# Universal-Power-Board.net
KiCad netlist of a schematic drawn in Altium Designer
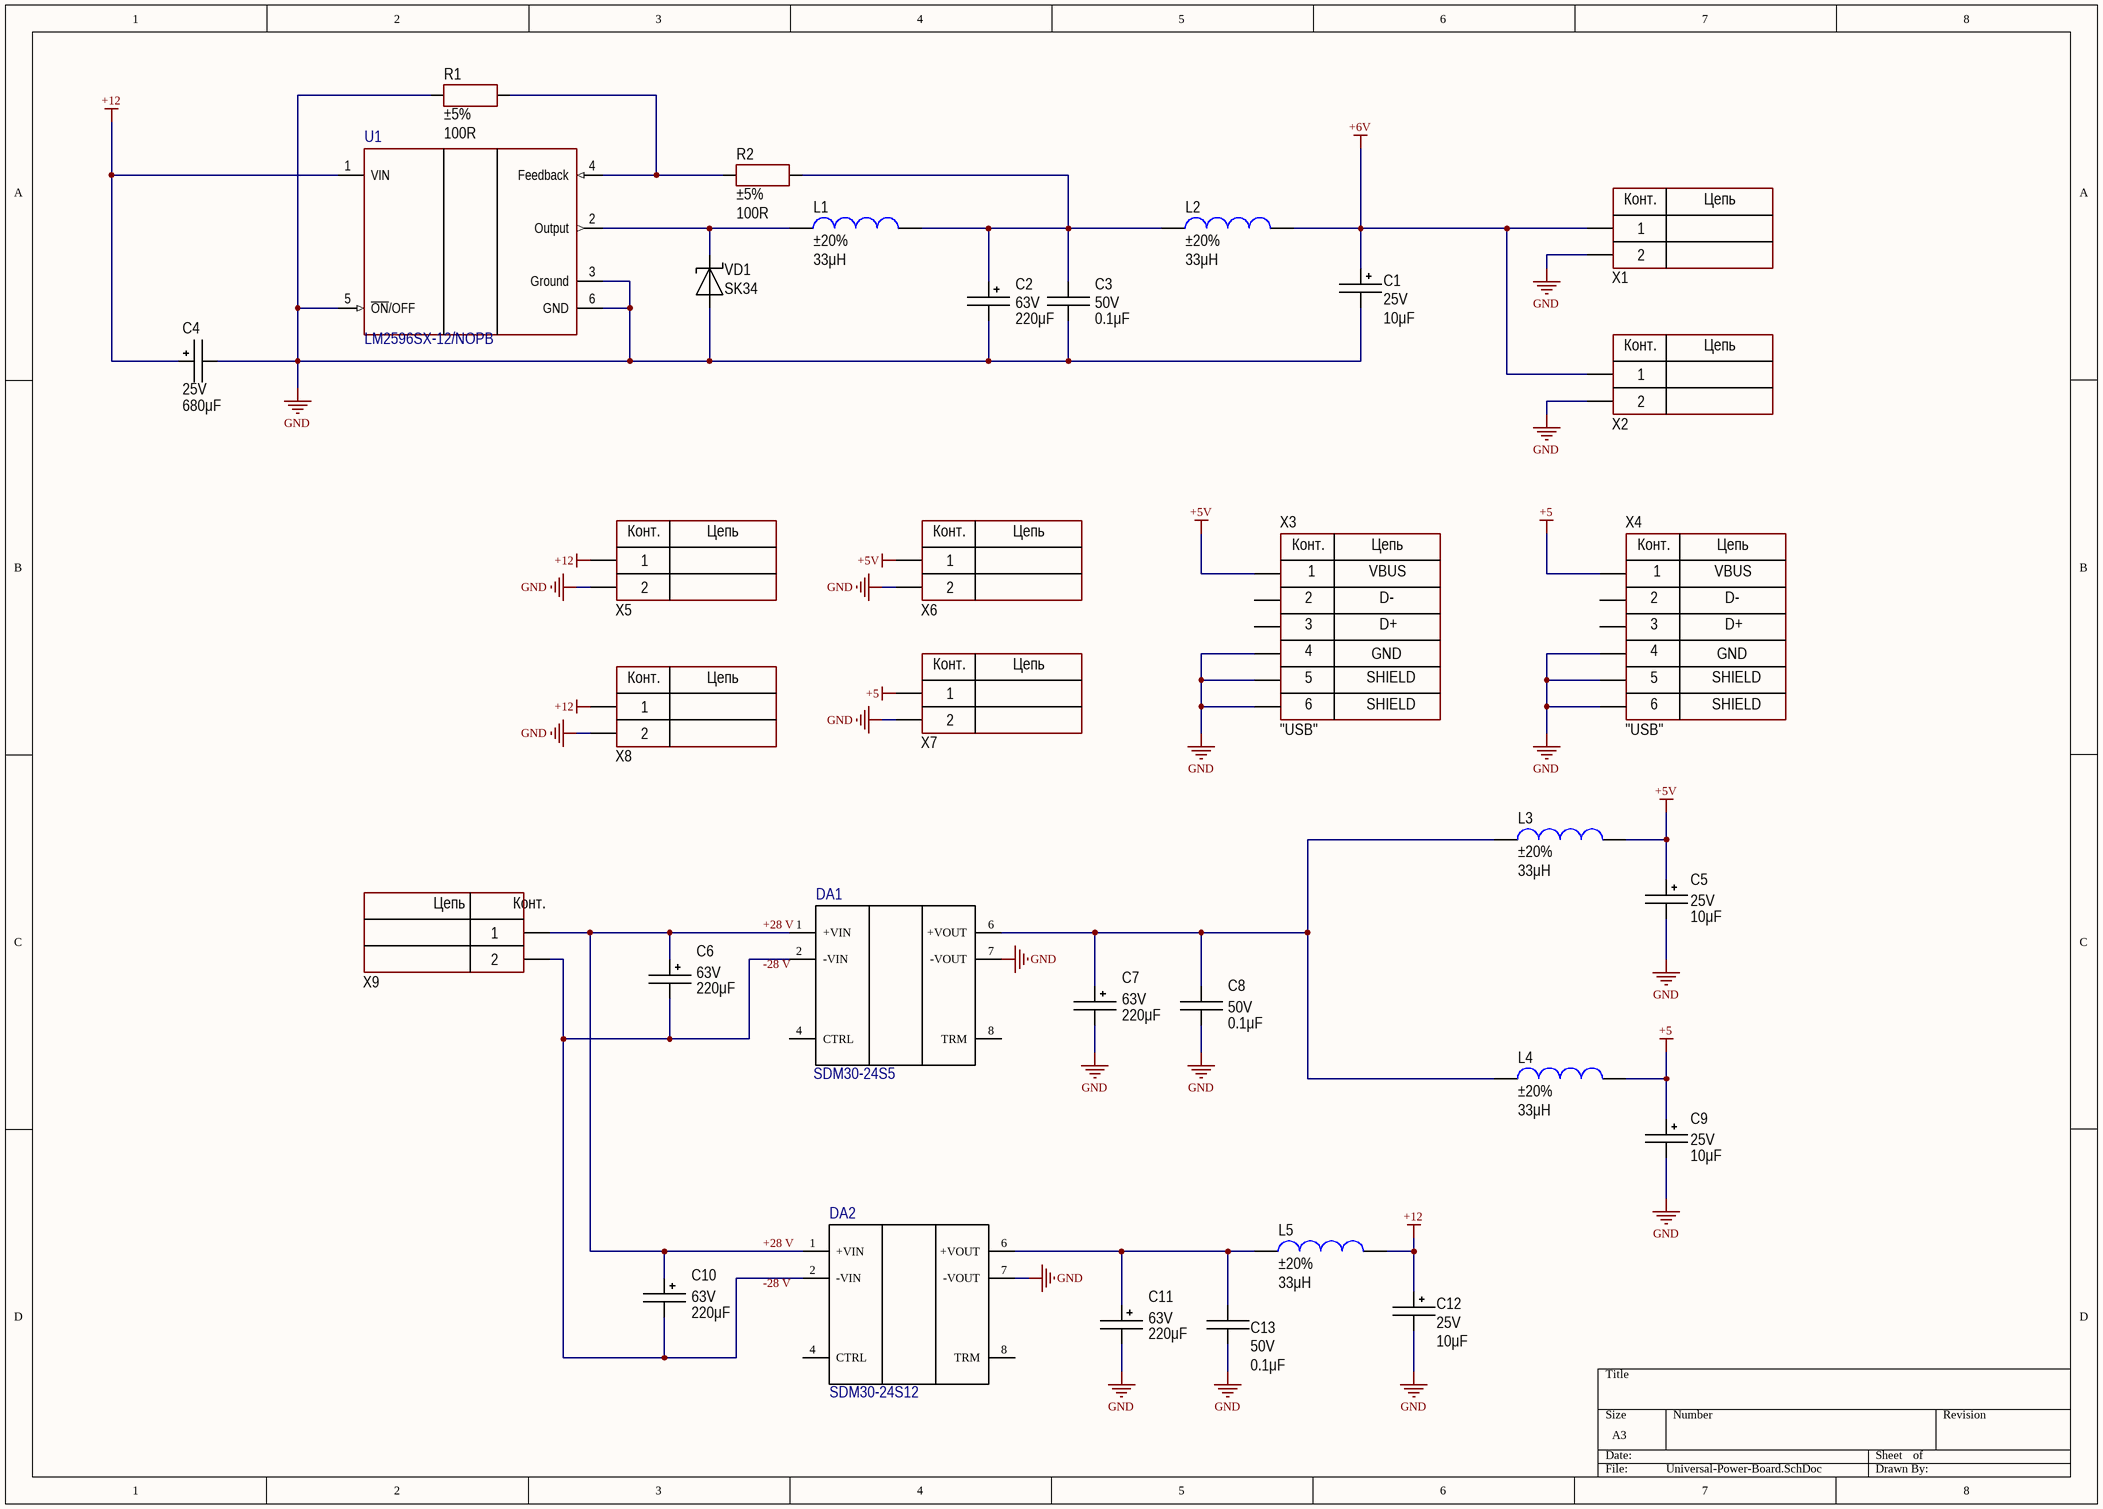
[diagram p0: Universal-Power-Board.SchDoc]

(export (version "E")
  (design (tool "Eeschema 10.0.6"))
  (components
    (comp (ref "C1")
      (value "10μF")
      (footprint "standard-case:CAP: D6.3C2.5H11")
      (fields
        (field (name "MANUFACTURER") "Wurth")
        (field (name "PARTNUMBER") "860080475013")
        (field (name "VALUEMANUFACTURERPARTNUMBER") "Aluminium capacitor, 10μF, 25V, ±20%, 54mOhm, 14x10x5 mm, -55...+105°C")
        (field (name "VOLTAGE") "25V")
      )
      (libsource (lib "capacitor") (part "Aluminium"))
    )
    (comp (ref "C2")
      (value "220μF")
      (footprint "standard-case:CAP: D10C5H16")
      (fields
        (field (name "MANUFACTURER") "Wurth")
        (field (name "PARTNUMBER") "860080475013")
        (field (name "VALUEMANUFACTURERPARTNUMBER") "Aluminium capacitor, 220μF, 63V, ±20%, 54mOhm, 14x10x5 mm, -55...+105°C")
        (field (name "VOLTAGE") "63V")
      )
      (libsource (lib "capacitor") (part "Aluminium"))
    )
    (comp (ref "C3")
      (value "0.1μF")
      (footprint "standard-case:CAP: 1206")
      (fields
        (field (name "MANUFACTURER") "Yageo")
        (field (name "PARTNUMBER") "CC1206KRX7R9BB104")
        (field (name "VALUEMANUFACTURERPARTNUMBER") "Ceramic capacitor, 0.1μF, X7R, ±10%, 50V, 1206, -55...+125°C")
        (field (name "VOLTAGE") "50V")
      )
      (libsource (lib "capacitor") (part "Ceramic_1206"))
    )
    (comp (ref "C4")
      (value "680μF")
      (footprint "standard-case:CAP: D10C5H16")
      (fields
        (field (name "MANUFACTURER") "Wurth")
        (field (name "PARTNUMBER") "860080475013")
        (field (name "VALUEMANUFACTURERPARTNUMBER") "Aluminium capacitor, 680μF, 25V, ±20%, 54mOhm, 14x10x5 mm, -55...+105°C")
        (field (name "VOLTAGE") "25V")
      )
      (libsource (lib "capacitor") (part "Aluminium"))
    )
    (comp (ref "C5")
      (value "10μF")
      (footprint "standard-case:CAP: D6.3C2.5H11")
      (fields
        (field (name "MANUFACTURER") "Wurth")
        (field (name "PARTNUMBER") "860080475013")
        (field (name "VALUEMANUFACTURERPARTNUMBER") "Aluminium capacitor, 10μF, 25V, ±20%, 54mOhm, 14x10x5 mm, -55...+105°C")
        (field (name "VOLTAGE") "25V")
      )
      (libsource (lib "capacitor") (part "Aluminium"))
    )
    (comp (ref "C6")
      (value "220μF")
      (footprint "standard-case:CAP: D10C5H16")
      (fields
        (field (name "MANUFACTURER") "Wurth")
        (field (name "PARTNUMBER") "860080475013")
        (field (name "VALUEMANUFACTURERPARTNUMBER") "Aluminium capacitor, 220μF, 63V, ±20%, 54mOhm, 14x10x5 mm, -55...+105°C")
        (field (name "VOLTAGE") "63V")
      )
      (libsource (lib "capacitor") (part "Aluminium"))
    )
    (comp (ref "C7")
      (value "220μF")
      (footprint "standard-case:CAP: D10C5H16")
      (fields
        (field (name "MANUFACTURER") "Wurth")
        (field (name "PARTNUMBER") "860080475013")
        (field (name "VALUEMANUFACTURERPARTNUMBER") "Aluminium capacitor, 220μF, 63V, ±20%, 54mOhm, 14x10x5 mm, -55...+105°C")
        (field (name "VOLTAGE") "63V")
      )
      (libsource (lib "capacitor") (part "Aluminium"))
    )
    (comp (ref "C8")
      (value "0.1μF")
      (footprint "standard-case:CAP: 1206")
      (fields
        (field (name "MANUFACTURER") "Yageo")
        (field (name "PARTNUMBER") "CC1206KRX7R9BB104")
        (field (name "VALUEMANUFACTURERPARTNUMBER") "Ceramic capacitor, 0.1μF, X7R, ±10%, 50V, 1206, -55...+125°C")
        (field (name "VOLTAGE") "50V")
      )
      (libsource (lib "capacitor") (part "Ceramic_1206"))
    )
    (comp (ref "C9")
      (value "10μF")
      (footprint "standard-case:CAP: D6.3C2.5H11")
      (fields
        (field (name "MANUFACTURER") "Wurth")
        (field (name "PARTNUMBER") "860080475013")
        (field (name "VALUEMANUFACTURERPARTNUMBER") "Aluminium capacitor, 10μF, 25V, ±20%, 54mOhm, 14x10x5 mm, -55...+105°C")
        (field (name "VOLTAGE") "25V")
      )
      (libsource (lib "capacitor") (part "Aluminium"))
    )
    (comp (ref "C10")
      (value "220μF")
      (footprint "standard-case:CAP: D10C5H16")
      (fields
        (field (name "MANUFACTURER") "Wurth")
        (field (name "PARTNUMBER") "860080475013")
        (field (name "VALUEMANUFACTURERPARTNUMBER") "Aluminium capacitor, 220μF, 63V, ±20%, 54mOhm, 14x10x5 mm, -55...+105°C")
        (field (name "VOLTAGE") "63V")
      )
      (libsource (lib "capacitor") (part "Aluminium"))
    )
    (comp (ref "C11")
      (value "220μF")
      (footprint "standard-case:CAP: D10C5H16")
      (fields
        (field (name "MANUFACTURER") "Wurth")
        (field (name "PARTNUMBER") "860080475013")
        (field (name "VALUEMANUFACTURERPARTNUMBER") "Aluminium capacitor, 220μF, 63V, ±20%, 54mOhm, 14x10x5 mm, -55...+105°C")
        (field (name "VOLTAGE") "63V")
      )
      (libsource (lib "capacitor") (part "Aluminium"))
    )
    (comp (ref "C12")
      (value "10μF")
      (footprint "standard-case:CAP: D6.3C2.5H11")
      (fields
        (field (name "MANUFACTURER") "Wurth")
        (field (name "PARTNUMBER") "860080475013")
        (field (name "VALUEMANUFACTURERPARTNUMBER") "Aluminium capacitor, 10μF, 25V, ±20%, 54mOhm, 14x10x5 mm, -55...+105°C")
        (field (name "VOLTAGE") "25V")
      )
      (libsource (lib "capacitor") (part "Aluminium"))
    )
    (comp (ref "C13")
      (value "0.1μF")
      (footprint "standard-case:CAP: 1206")
      (fields
        (field (name "MANUFACTURER") "Yageo")
        (field (name "PARTNUMBER") "CC1206KRX7R9BB104")
        (field (name "VALUEMANUFACTURERPARTNUMBER") "Ceramic capacitor, 0.1μF, X7R, ±10%, 50V, 1206, -55...+125°C")
        (field (name "VOLTAGE") "50V")
      )
      (libsource (lib "capacitor") (part "Ceramic_1206"))
    )
    (comp (ref "DA1")
      (value "SDM30-24S5")
      (footprint "SDM3024S5")
      (description "Power Supply")
      (libsource (lib "SDM30-24S5") (part "SDM30-24S5"))
    )
    (comp (ref "DA2")
      (value "SDM30-24S12")
      (footprint "SDM3024S12")
      (description "Power Supply")
      (libsource (lib "SDM30-24S12") (part "SDM30-24S12"))
    )
    (comp (ref "L1")
      (value "33μH")
      (footprint "SRR1208-101YL")
      (fields
        (field (name "MANUFACTURER") "Bourns")
        (field (name "PARTNUMBER") "SDR0403-4R7ML")
        (field (name "VALUEMANUFACTURERPARTNUMBER") "Fixed inductor, 33μH, ±20%, SDR0403, 1.7A, -40...+125°C")
        (field (name "TOLERANCE") "±20%")
      )
      (libsource (lib "SRR1208-101YL") (part "Inductor_SDR0403"))
    )
    (comp (ref "L2")
      (value "33μH")
      (footprint "SRR1208-101YL")
      (fields
        (field (name "MANUFACTURER") "Bourns")
        (field (name "PARTNUMBER") "SDR0403-4R7ML")
        (field (name "VALUEMANUFACTURERPARTNUMBER") "Fixed inductor, 33μH, ±20%, SDR0403, 1.7A, -40...+125°C")
        (field (name "TOLERANCE") "±20%")
      )
      (libsource (lib "SRR1208-101YL") (part "Inductor_SDR0403"))
    )
    (comp (ref "L3")
      (value "33μH")
      (footprint "SRR1208-101YL")
      (fields
        (field (name "MANUFACTURER") "Bourns")
        (field (name "PARTNUMBER") "SDR0403-4R7ML")
        (field (name "VALUEMANUFACTURERPARTNUMBER") "Fixed inductor, 33μH, ±20%, SDR0403, 1.7A, -40...+125°C")
        (field (name "TOLERANCE") "±20%")
      )
      (libsource (lib "SRR1208-101YL") (part "Inductor_SDR0403"))
    )
    (comp (ref "L4")
      (value "33μH")
      (footprint "SRR1208-101YL")
      (fields
        (field (name "MANUFACTURER") "Bourns")
        (field (name "PARTNUMBER") "SDR0403-4R7ML")
        (field (name "VALUEMANUFACTURERPARTNUMBER") "Fixed inductor, 33μH, ±20%, SDR0403, 1.7A, -40...+125°C")
        (field (name "TOLERANCE") "±20%")
      )
      (libsource (lib "SRR1208-101YL") (part "Inductor_SDR0403"))
    )
    (comp (ref "L5")
      (value "33μH")
      (footprint "SRR1208-101YL")
      (fields
        (field (name "MANUFACTURER") "Bourns")
        (field (name "PARTNUMBER") "SDR0403-4R7ML")
        (field (name "VALUEMANUFACTURERPARTNUMBER") "Fixed inductor, 33μH, ±20%, SDR0403, 1.7A, -40...+125°C")
        (field (name "TOLERANCE") "±20%")
      )
      (libsource (lib "SRR1208-101YL") (part "Inductor_SDR0403"))
    )
    (comp (ref "R1")
      (value "100R")
      (footprint "standard-case:RES: 1206")
      (fields
        (field (name "MANUFACTURER") "Yageo")
        (field (name "PARTNUMBER") "RC1206JR-07100RL")
        (field (name "VALUEMANUFACTURERPARTNUMBER") "Resistor film, 100R, ±5%, 1206, 0.25W, -55...+125°C")
        (field (name "TOLERANCE") "±5%")
      )
      (libsource (lib "resistor") (part "Resistor_1206"))
    )
    (comp (ref "R2")
      (value "100R")
      (footprint "standard-case:RES: 1206")
      (fields
        (field (name "MANUFACTURER") "Yageo")
        (field (name "PARTNUMBER") "RC1206JR-07100RL")
        (field (name "VALUEMANUFACTURERPARTNUMBER") "Resistor film, 100R, ±5%, 1206, 0.25W, -55...+125°C")
        (field (name "TOLERANCE") "±5%")
      )
      (libsource (lib "resistor") (part "Resistor_1206"))
    )
    (comp (ref "U1")
      (value "LM2596SX-12/NOPB")
      (footprint "FP-KTT0005B-MFG")
      (description "IC REG BUCK 12V 3A TO263-5")
      (fields
        (field (name "MANUFACTURER") "Texas Instruments")
        (field (name "OCTOPART") "https://octopart.com/lm2596sx-12%2Fnopb-texas+instruments-24812942")
      )
      (libsource (lib "LM2596SX-12NOPB") (part "CMP-04918-000013-1"))
    )
    (comp (ref "VD1")
      (value "~")
      (footprint "standard-case:DIODE: SMC")
      (fields
        (field (name "MANUFACTURER") "Diodes Incorporated")
        (field (name "VALUEMANUFACTURERPARTNUMBER") "Schottky diode, 80V, 500mA, 1V, 15pF, SOD-123, -55...+150°C")
        (field (name "VOLTAGE") "80V")
        (field (name "PARTNUMBER") "SK34")
      )
      (libsource (lib "diode") (part "Schottky_single"))
    )
    (comp (ref "X1")
      (value "~")
      (footprint "2EDGR-5.08-02P")
      (fields
        (field (name "MANUFACTURER") "Connfly")
        (field (name "VALUEMANUFACTURERPARTNUMBER") "Connector, 6pin, 2.54mm, 500VAC, 3A")
        (field (name "PARTNUMBER") "PBS-6")
      )
      (libsource (lib "K3NG_SCH_Libs") (part "2EDGR-5.08-02P"))
    )
    (comp (ref "X2")
      (value "~")
      (footprint "2EDGR-5.08-02P")
      (fields
        (field (name "MANUFACTURER") "Connfly")
        (field (name "VALUEMANUFACTURERPARTNUMBER") "Connector, 6pin, 2.54mm, 500VAC, 3A")
        (field (name "PARTNUMBER") "PBS-6")
      )
      (libsource (lib "K3NG_SCH_Libs") (part "2EDGR-5.08-02P"))
    )
    (comp (ref "X3")
      (value "~")
      (footprint "FP-292303-4-MFG")
      (fields
        (field (name "MANUFACTURER") "Hirose Electric")
        (field (name "VALUEMANUFACTURERPARTNUMBER") "USB micro B")
        (field (name "PARTNUMBER") "ZX62-B-5PA")
        (field (name "COMMENTTEXT") "\"USB\"")
      )
      (libsource (lib "292303-4") (part "Connector_USB_micro_B"))
    )
    (comp (ref "X4")
      (value "~")
      (footprint "FP-292303-4-MFG")
      (fields
        (field (name "MANUFACTURER") "Hirose Electric")
        (field (name "VALUEMANUFACTURERPARTNUMBER") "USB micro B")
        (field (name "PARTNUMBER") "ZX62-B-5PA")
        (field (name "COMMENTTEXT") "\"USB\"")
      )
      (libsource (lib "292303-4") (part "Connector_USB_micro_B"))
    )
    (comp (ref "X5")
      (value "~")
      (footprint "2EDGR-5.08-02P")
      (fields
        (field (name "MANUFACTURER") "Connfly")
        (field (name "VALUEMANUFACTURERPARTNUMBER") "Connector, 6pin, 2.54mm, 500VAC, 3A")
        (field (name "PARTNUMBER") "PBS-6")
      )
      (libsource (lib "K3NG_SCH_Libs") (part "2EDGR-5.08-02P"))
    )
    (comp (ref "X6")
      (value "~")
      (footprint "2EDGR-5.08-02P")
      (fields
        (field (name "MANUFACTURER") "Connfly")
        (field (name "VALUEMANUFACTURERPARTNUMBER") "Connector, 6pin, 2.54mm, 500VAC, 3A")
        (field (name "PARTNUMBER") "PBS-6")
      )
      (libsource (lib "K3NG_SCH_Libs") (part "2EDGR-5.08-02P"))
    )
    (comp (ref "X7")
      (value "~")
      (footprint "2EDGR-5.08-02P")
      (fields
        (field (name "MANUFACTURER") "Connfly")
        (field (name "VALUEMANUFACTURERPARTNUMBER") "Connector, 6pin, 2.54mm, 500VAC, 3A")
        (field (name "PARTNUMBER") "PBS-6")
      )
      (libsource (lib "K3NG_SCH_Libs") (part "2EDGR-5.08-02P"))
    )
    (comp (ref "X8")
      (value "~")
      (footprint "2EDGR-5.08-02P")
      (fields
        (field (name "MANUFACTURER") "Connfly")
        (field (name "VALUEMANUFACTURERPARTNUMBER") "Connector, 6pin, 2.54mm, 500VAC, 3A")
        (field (name "PARTNUMBER") "PBS-6")
      )
      (libsource (lib "K3NG_SCH_Libs") (part "2EDGR-5.08-02P"))
    )
    (comp (ref "X9")
      (value "~")
      (footprint "2EDGR-5.08-02P")
      (fields
        (field (name "MANUFACTURER") "Connfly")
        (field (name "VALUEMANUFACTURERPARTNUMBER") "Connector, 6pin, 2.54mm, 500VAC, 3A")
        (field (name "PARTNUMBER") "PBS-6")
      )
      (libsource (lib "") (part "2EDGR-5.08-02P_1"))
    )
  )
  (nets
    (net (code "1") (name "+5") (class "Default")
      (node (ref "C9") (pin "1") (pinfunction "1_1") (pintype "passive"))
      (node (ref "L4") (pin "1") (pinfunction "1_1") (pintype "passive"))
      (node (ref "X4") (pin "1") (pintype "passive"))
      (node (ref "X7") (pin "1") (pinfunction "1_1") (pintype "passive"))
    )
    (net (code "2") (name "+5V") (class "Default")
      (node (ref "C5") (pin "1") (pinfunction "1_1") (pintype "passive"))
      (node (ref "L3") (pin "1") (pinfunction "1_1") (pintype "passive"))
      (node (ref "X3") (pin "1") (pintype "passive"))
      (node (ref "X6") (pin "1") (pinfunction "1_1") (pintype "passive"))
    )
    (net (code "3") (name "+6V") (class "Default")
      (node (ref "C1") (pin "1") (pinfunction "1_1") (pintype "passive"))
      (node (ref "L2") (pin "1") (pinfunction "1_1") (pintype "passive"))
      (node (ref "X1") (pin "1") (pinfunction "1_1") (pintype "passive"))
      (node (ref "X2") (pin "1") (pinfunction "1_1") (pintype "passive"))
    )
    (net (code "4") (name "+12") (class "Default")
      (node (ref "C12") (pin "1") (pinfunction "1_1") (pintype "passive"))
      (node (ref "C4") (pin "1") (pinfunction "1_1") (pintype "passive"))
      (node (ref "L5") (pin "1") (pinfunction "1_1") (pintype "passive"))
      (node (ref "U1") (pin "1") (pinfunction "VIN_1") (pintype "power_in"))
      (node (ref "X5") (pin "1") (pinfunction "1_1") (pintype "passive"))
      (node (ref "X8") (pin "1") (pinfunction "1_1") (pintype "passive"))
    )
    (net (code "5") (name "/+28 V") (class "Default")
      (node (ref "C10") (pin "1") (pinfunction "1_1") (pintype "passive"))
      (node (ref "C6") (pin "1") (pinfunction "1_1") (pintype "passive"))
      (node (ref "DA1") (pin "1") (pinfunction "+VIN_1") (pintype "passive"))
      (node (ref "DA2") (pin "1") (pinfunction "+VIN_1") (pintype "passive"))
      (node (ref "X9") (pin "1") (pinfunction "1_1") (pintype "passive"))
    )
    (net (code "7") (name "GND") (class "Default")
      (node (ref "C1") (pin "2") (pinfunction "2_2") (pintype "passive"))
      (node (ref "C11") (pin "2") (pinfunction "2_2") (pintype "passive"))
      (node (ref "C12") (pin "2") (pinfunction "2_2") (pintype "passive"))
      (node (ref "C13") (pin "1") (pinfunction "1_1") (pintype "passive"))
      (node (ref "C2") (pin "2") (pinfunction "2_2") (pintype "passive"))
      (node (ref "C3") (pin "1") (pinfunction "1_1") (pintype "passive"))
      (node (ref "C4") (pin "2") (pinfunction "2_2") (pintype "passive"))
      (node (ref "C5") (pin "2") (pinfunction "2_2") (pintype "passive"))
      (node (ref "C7") (pin "2") (pinfunction "2_2") (pintype "passive"))
      (node (ref "C8") (pin "1") (pinfunction "1_1") (pintype "passive"))
      (node (ref "C9") (pin "2") (pinfunction "2_2") (pintype "passive"))
      (node (ref "DA1") (pin "7") (pinfunction "-VOUT_7") (pintype "passive"))
      (node (ref "DA2") (pin "7") (pinfunction "-VOUT_7") (pintype "passive"))
      (node (ref "R1") (pin "1") (pinfunction "1_1") (pintype "passive"))
      (node (ref "U1") (pin "3") (pinfunction "Ground_3") (pintype "power_in"))
      (node (ref "U1") (pin "5") (pinfunction "~{ON}/OFF_5") (pintype "input"))
      (node (ref "U1") (pin "6") (pinfunction "GND_6") (pintype "power_in"))
      (node (ref "VD1") (pin "1") (pinfunction "1_1") (pintype "passive"))
      (node (ref "X1") (pin "2") (pinfunction "2_2") (pintype "passive"))
      (node (ref "X2") (pin "2") (pinfunction "2_2") (pintype "passive"))
      (node (ref "X3") (pin "4") (pinfunction "4_4") (pintype "passive"))
      (node (ref "X3") (pin "5") (pinfunction "5_5") (pintype "passive"))
      (node (ref "X3") (pin "6") (pinfunction "6_6") (pintype "passive"))
      (node (ref "X4") (pin "4") (pinfunction "4_4") (pintype "passive"))
      (node (ref "X4") (pin "5") (pinfunction "5_5") (pintype "passive"))
      (node (ref "X4") (pin "6") (pinfunction "6_6") (pintype "passive"))
      (node (ref "X5") (pin "2") (pinfunction "2_2") (pintype "passive"))
      (node (ref "X6") (pin "2") (pinfunction "2_2") (pintype "passive"))
      (node (ref "X7") (pin "2") (pinfunction "2_2") (pintype "passive"))
      (node (ref "X8") (pin "2") (pinfunction "2_2") (pintype "passive"))
    )
    (net (code "8") (name "Net-(C2-Pad1)") (class "Default")
      (node (ref "C2") (pin "1") (pinfunction "1_1") (pintype "passive"))
      (node (ref "C3") (pin "2") (pinfunction "2_2") (pintype "passive"))
      (node (ref "L1") (pin "1") (pinfunction "1_1") (pintype "passive"))
      (node (ref "L2") (pin "2") (pinfunction "2_2") (pintype "passive"))
      (node (ref "R2") (pin "2") (pinfunction "2_2") (pintype "passive"))
    )
    (net (code "9") (name "Net-(DA1-+VOUT)") (class "Default")
      (node (ref "C7") (pin "1") (pinfunction "1_1") (pintype "passive"))
      (node (ref "C8") (pin "2") (pinfunction "2_2") (pintype "passive"))
      (node (ref "DA1") (pin "6") (pinfunction "+VOUT_6") (pintype "passive"))
      (node (ref "L3") (pin "2") (pinfunction "2_2") (pintype "passive"))
      (node (ref "L4") (pin "2") (pinfunction "2_2") (pintype "passive"))
    )
    (net (code "10") (name "Net-(DA1--VIN)") (class "Default")
      (node (ref "C10") (pin "2") (pinfunction "2_2") (pintype "passive"))
      (node (ref "C6") (pin "2") (pinfunction "2_2") (pintype "passive"))
      (node (ref "DA1") (pin "2") (pinfunction "-VIN_2") (pintype "passive"))
      (node (ref "DA2") (pin "2") (pinfunction "-VIN_2") (pintype "passive"))
      (node (ref "X9") (pin "2") (pinfunction "2_2") (pintype "passive"))
    )
    (net (code "11") (name "Net-(DA2-+VOUT)") (class "Default")
      (node (ref "C11") (pin "1") (pinfunction "1_1") (pintype "passive"))
      (node (ref "C13") (pin "2") (pinfunction "2_2") (pintype "passive"))
      (node (ref "DA2") (pin "6") (pinfunction "+VOUT_6") (pintype "passive"))
      (node (ref "L5") (pin "2") (pinfunction "2_2") (pintype "passive"))
    )
    (net (code "12") (name "Net-(U1-Feedback)") (class "Default")
      (node (ref "R1") (pin "2") (pinfunction "2_2") (pintype "passive"))
      (node (ref "R2") (pin "1") (pinfunction "1_1") (pintype "passive"))
      (node (ref "U1") (pin "4") (pinfunction "Feedback_4") (pintype "input"))
    )
    (net (code "13") (name "Net-(U1-Output)") (class "Default")
      (node (ref "L1") (pin "2") (pinfunction "2_2") (pintype "passive"))
      (node (ref "U1") (pin "2") (pinfunction "Output_2") (pintype "output"))
      (node (ref "VD1") (pin "2") (pinfunction "2_2") (pintype "passive"))
    )
    (net (code "14") (name "unconnected-(DA1-CTRL-Pad4)") (class "Default")
      (node (ref "DA1") (pin "4") (pinfunction "CTRL_4") (pintype "passive"))
    )
    (net (code "15") (name "unconnected-(DA1-TRM-Pad8)") (class "Default")
      (node (ref "DA1") (pin "8") (pinfunction "TRM_8") (pintype "passive"))
    )
    (net (code "16") (name "unconnected-(DA2-CTRL-Pad4)") (class "Default")
      (node (ref "DA2") (pin "4") (pinfunction "CTRL_4") (pintype "passive"))
    )
    (net (code "17") (name "unconnected-(DA2-TRM-Pad8)") (class "Default")
      (node (ref "DA2") (pin "8") (pinfunction "TRM_8") (pintype "passive"))
    )
    (net (code "18") (name "unconnected-(X3-Pad2)") (class "Default")
      (node (ref "X3") (pin "2") (pinfunction "2_2") (pintype "passive"))
    )
    (net (code "19") (name "unconnected-(X3-Pad3)") (class "Default")
      (node (ref "X3") (pin "3") (pinfunction "3_3") (pintype "passive"))
    )
    (net (code "20") (name "unconnected-(X4-Pad2)") (class "Default")
      (node (ref "X4") (pin "2") (pinfunction "2_2") (pintype "passive"))
    )
    (net (code "21") (name "unconnected-(X4-Pad3)") (class "Default")
      (node (ref "X4") (pin "3") (pinfunction "3_3") (pintype "passive"))
    )
  )
)
